# V2.net
KiCad netlist of a schematic drawn in Altium Designer
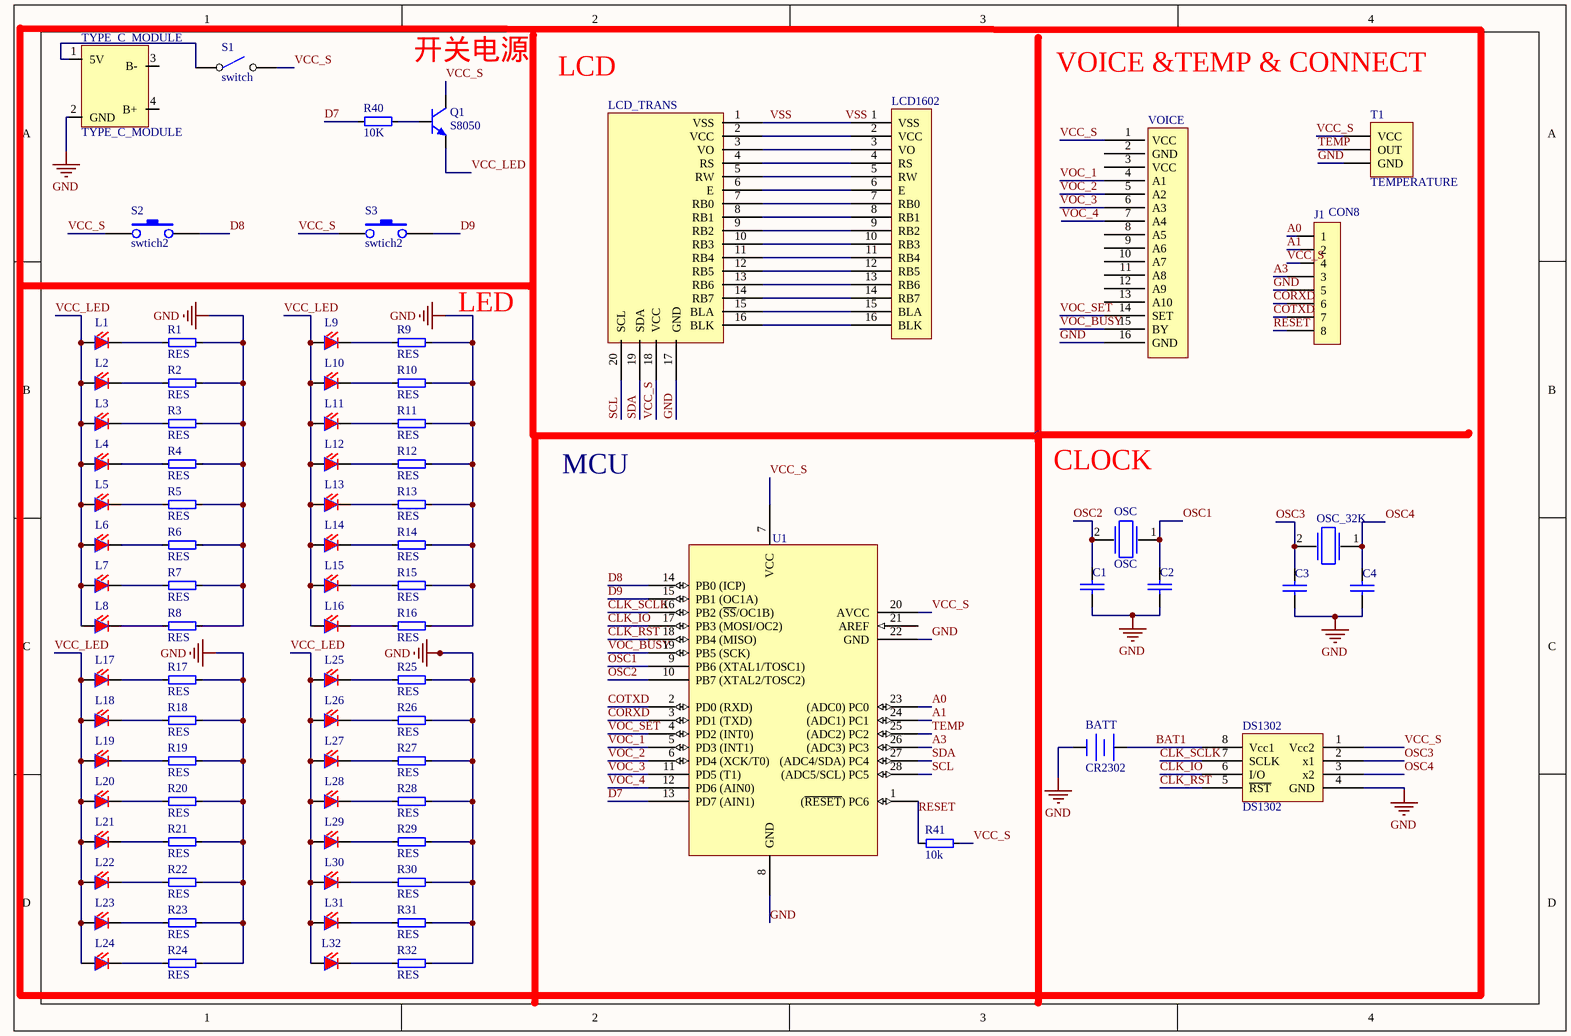
[diagram p0: 生日礼物V2.SchDoc]

(export (version "E")
  (design (tool "Eeschema 10.0.6"))
  (components
    (comp (ref "BATT")
      (value "CR2302")
      (footprint "CR2032_C")
      (description "Multicell Battery")
      (fields (field (name "PUBLISHER") "Altium Limited"))
      (libsource (lib "最小系统") (part "BATTERY"))
    )
    (comp (ref "C1") (value "~") (footprint "CAP") (libsource (lib "最小系统") (part "CAP")))
    (comp (ref "C2") (value "~") (footprint "CAP") (libsource (lib "最小系统") (part "CAP")))
    (comp (ref "C3") (value "~") (footprint "CAP") (libsource (lib "最小系统") (part "CAP")))
    (comp (ref "C4") (value "~") (footprint "CAP") (libsource (lib "最小系统") (part "CAP")))
    (comp (ref "DS1302") (value "DS1302") (footprint "DS1302") (libsource (lib "最小系统") (part "DS1302")))
    (comp (ref "J1") (value "CON8") (footprint "CON8") (libsource (lib "最小系统") (part "CON8")))
    (comp (ref "L1") (value "~") (footprint "LED 5MM-Y") (libsource (lib "最小系统") (part "LED")))
    (comp (ref "L2") (value "~") (footprint "LED 5MM-Y") (libsource (lib "最小系统") (part "LED")))
    (comp (ref "L3") (value "~") (footprint "LED 5MM-Y") (libsource (lib "最小系统") (part "LED")))
    (comp (ref "L4") (value "~") (footprint "LED 5MM-Y") (libsource (lib "最小系统") (part "LED")))
    (comp (ref "L5") (value "~") (footprint "LED 5MM-Y") (libsource (lib "最小系统") (part "LED")))
    (comp (ref "L6") (value "~") (footprint "LED 5MM-Y") (libsource (lib "最小系统") (part "LED")))
    (comp (ref "L7") (value "~") (footprint "LED 5MM-Y") (libsource (lib "最小系统") (part "LED")))
    (comp (ref "L8") (value "~") (footprint "LED 5MM-Y") (libsource (lib "最小系统") (part "LED")))
    (comp (ref "L9") (value "~") (footprint "LED 5MM-Y") (libsource (lib "最小系统") (part "LED")))
    (comp (ref "L10") (value "~") (footprint "LED 5MM-Y") (libsource (lib "最小系统") (part "LED")))
    (comp (ref "L11") (value "~") (footprint "LED 5MM-Y") (libsource (lib "最小系统") (part "LED")))
    (comp (ref "L12") (value "~") (footprint "LED 5MM-Y") (libsource (lib "最小系统") (part "LED")))
    (comp (ref "L13") (value "~") (footprint "LED 5MM-Y") (libsource (lib "最小系统") (part "LED")))
    (comp (ref "L14") (value "~") (footprint "LED 5MM-Y") (libsource (lib "最小系统") (part "LED")))
    (comp (ref "L15") (value "~") (footprint "LED 5MM-Y") (libsource (lib "最小系统") (part "LED")))
    (comp (ref "L16") (value "~") (footprint "LED 5MM-Y") (libsource (lib "最小系统") (part "LED")))
    (comp (ref "L17") (value "~") (footprint "LED 5MM-Y") (libsource (lib "最小系统") (part "LED")))
    (comp (ref "L18") (value "~") (footprint "LED 5MM-Y") (libsource (lib "最小系统") (part "LED")))
    (comp (ref "L19") (value "~") (footprint "LED 5MM-Y") (libsource (lib "最小系统") (part "LED")))
    (comp (ref "L20") (value "~") (footprint "LED 5MM-Y") (libsource (lib "最小系统") (part "LED")))
    (comp (ref "L21") (value "~") (footprint "LED 5MM-Y") (libsource (lib "最小系统") (part "LED")))
    (comp (ref "L22") (value "~") (footprint "LED 5MM-Y") (libsource (lib "最小系统") (part "LED")))
    (comp (ref "L23") (value "~") (footprint "LED 5MM-Y") (libsource (lib "最小系统") (part "LED")))
    (comp (ref "L24") (value "~") (footprint "LED 5MM-Y") (libsource (lib "最小系统") (part "LED")))
    (comp (ref "L25") (value "~") (footprint "LED 5MM-Y") (libsource (lib "最小系统") (part "LED")))
    (comp (ref "L26") (value "~") (footprint "LED 5MM-Y") (libsource (lib "最小系统") (part "LED")))
    (comp (ref "L27") (value "~") (footprint "LED 5MM-Y") (libsource (lib "最小系统") (part "LED")))
    (comp (ref "L28") (value "~") (footprint "LED 5MM-Y") (libsource (lib "最小系统") (part "LED")))
    (comp (ref "L29") (value "~") (footprint "LED 5MM-Y") (libsource (lib "最小系统") (part "LED")))
    (comp (ref "L30") (value "~") (footprint "LED 5MM-Y") (libsource (lib "最小系统") (part "LED")))
    (comp (ref "L31") (value "~") (footprint "LED 5MM-Y") (libsource (lib "最小系统") (part "LED")))
    (comp (ref "L32") (value "~") (footprint "LED 5MM-Y") (libsource (lib "最小系统") (part "LED")))
    (comp (ref "LCD1602") (value "~") (footprint "LCD1602") (libsource (lib "最小系统") (part "LCD1602")))
    (comp (ref "LCD_TRANS") (value "~") (footprint "LCD-TRANS") (libsource (lib "最小系统") (part "LCD_TRANS")))
    (comp (ref "OSC")
      (value "OSC")
      (footprint "OSC HC-49U")
      (description "晶振 32.768KHZ")
      (libsource (lib "最小系统") (part "OSC"))
    )
    (comp (ref "OSC_32K") (value "~") (footprint "osc_32.768K") (libsource (lib "生日礼物V2") (part "OSC_32K")))
    (comp (ref "Q1")
      (value "S8050")
      (footprint "TO92")
      (description "高频放大-NPN型")
      (fields (field (name "版权归属") "源创客"))
      (libsource (lib "最小系统") (part "8050-DIP"))
    )
    (comp (ref "R1") (value "RES") (footprint "0805R") (libsource (lib "最小系统") (part "RES")))
    (comp (ref "R2") (value "RES") (footprint "0805R") (libsource (lib "最小系统") (part "RES")))
    (comp (ref "R3") (value "RES") (footprint "0805R") (libsource (lib "最小系统") (part "RES")))
    (comp (ref "R4") (value "RES") (footprint "0805R") (libsource (lib "最小系统") (part "RES")))
    (comp (ref "R5") (value "RES") (footprint "0805R") (libsource (lib "最小系统") (part "RES")))
    (comp (ref "R6") (value "RES") (footprint "0805R") (libsource (lib "最小系统") (part "RES")))
    (comp (ref "R7") (value "RES") (footprint "0805R") (libsource (lib "最小系统") (part "RES")))
    (comp (ref "R8") (value "RES") (footprint "0805R") (libsource (lib "最小系统") (part "RES")))
    (comp (ref "R9") (value "RES") (footprint "0805R") (libsource (lib "最小系统") (part "RES")))
    (comp (ref "R10") (value "RES") (footprint "0805R") (libsource (lib "最小系统") (part "RES")))
    (comp (ref "R11") (value "RES") (footprint "0805R") (libsource (lib "最小系统") (part "RES")))
    (comp (ref "R12") (value "RES") (footprint "0805R") (libsource (lib "最小系统") (part "RES")))
    (comp (ref "R13") (value "RES") (footprint "0805R") (libsource (lib "最小系统") (part "RES")))
    (comp (ref "R14") (value "RES") (footprint "0805R") (libsource (lib "最小系统") (part "RES")))
    (comp (ref "R15") (value "RES") (footprint "0805R") (libsource (lib "最小系统") (part "RES")))
    (comp (ref "R16") (value "RES") (footprint "0805R") (libsource (lib "最小系统") (part "RES")))
    (comp (ref "R17") (value "RES") (footprint "0805R") (libsource (lib "最小系统") (part "RES")))
    (comp (ref "R18") (value "RES") (footprint "0805R") (libsource (lib "最小系统") (part "RES")))
    (comp (ref "R19") (value "RES") (footprint "0805R") (libsource (lib "最小系统") (part "RES")))
    (comp (ref "R20") (value "RES") (footprint "0805R") (libsource (lib "最小系统") (part "RES")))
    (comp (ref "R21") (value "RES") (footprint "0805R") (libsource (lib "最小系统") (part "RES")))
    (comp (ref "R22") (value "RES") (footprint "0805R") (libsource (lib "最小系统") (part "RES")))
    (comp (ref "R23") (value "RES") (footprint "0805R") (libsource (lib "最小系统") (part "RES")))
    (comp (ref "R24") (value "RES") (footprint "0805R") (libsource (lib "最小系统") (part "RES")))
    (comp (ref "R25") (value "RES") (footprint "0805R") (libsource (lib "最小系统") (part "RES")))
    (comp (ref "R26") (value "RES") (footprint "0805R") (libsource (lib "最小系统") (part "RES")))
    (comp (ref "R27") (value "RES") (footprint "0805R") (libsource (lib "最小系统") (part "RES")))
    (comp (ref "R28") (value "RES") (footprint "0805R") (libsource (lib "最小系统") (part "RES")))
    (comp (ref "R29") (value "RES") (footprint "0805R") (libsource (lib "最小系统") (part "RES")))
    (comp (ref "R30") (value "RES") (footprint "0805R") (libsource (lib "最小系统") (part "RES")))
    (comp (ref "R31") (value "RES") (footprint "0805R") (libsource (lib "最小系统") (part "RES")))
    (comp (ref "R32") (value "RES") (footprint "0805R") (libsource (lib "最小系统") (part "RES")))
    (comp (ref "R40") (value "10K") (footprint "0805R") (libsource (lib "最小系统") (part "RES")))
    (comp (ref "R41") (value "10k") (footprint "0805R") (libsource (lib "最小系统") (part "RES")))
    (comp (ref "S1")
      (value "switch")
      (footprint "switch")
      (description "主开关")
      (libsource (lib "最小系统") (part "switch"))
    )
    (comp (ref "S2")
      (value "swtich2")
      (footprint "switch")
      (description "按钮触发")
      (libsource (lib "最小系统") (part "swtich"))
    )
    (comp (ref "S3") (value "swtich2") (footprint "switch") (libsource (lib "最小系统") (part "swtich")))
    (comp (ref "T1")
      (value "TEMPERATURE")
      (footprint "TEMP_SENSOR")
      (description "温度传感器")
      (libsource (lib "最小系统") (part "TEMPERATURE"))
    )
    (comp (ref "TYPE_C_MODULE")
      (value "TYPE_C_MODULE")
      (footprint "TYPE_C_Module")
      (libsource (lib "最小系统") (part "TYPE_C_MODULE"))
    )
    (comp (ref "U1")
      (value "~")
      (footprint "DIP28")
      (description "Atmel Microcontroller - Library created by carel..  <www.mpfreezone.com>")
      (libsource (lib "最小系统") (part "ATMEGA8_DIP28"))
    )
    (comp (ref "VOICE") (value "~") (footprint "VOICE") (libsource (lib "最小系统") (part "VOICE")))
  )
  (nets
    (net (code "1") (name "/A0") (class "Default")
      (node (ref "J1") (pin "1") (pinfunction "1_1") (pintype "passive"))
      (node (ref "U1") (pin "23") (pinfunction "(ADC0)_PC0_23") (pintype "bidirectional"))
    )
    (net (code "2") (name "/A1") (class "Default")
      (node (ref "J1") (pin "2") (pinfunction "2_2") (pintype "passive"))
      (node (ref "U1") (pin "24") (pinfunction "(ADC1)_PC1_24") (pintype "bidirectional"))
    )
    (net (code "3") (name "/A3") (class "Default")
      (node (ref "J1") (pin "3") (pinfunction "3_3") (pintype "passive"))
      (node (ref "U1") (pin "26") (pinfunction "(ADC3)_PC3_26") (pintype "bidirectional"))
    )
    (net (code "4") (name "/BAT1") (class "Default")
      (node (ref "BATT") (pin "1") (pinfunction "+_1") (pintype "passive"))
      (node (ref "DS1302") (pin "8") (pinfunction "Vcc1_8") (pintype "passive"))
    )
    (net (code "5") (name "/CLK_IO") (class "Default")
      (node (ref "DS1302") (pin "6") (pinfunction "I/O_6") (pintype "passive"))
      (node (ref "U1") (pin "17") (pinfunction "PB3_(MOSI/OC2)_17") (pintype "bidirectional"))
    )
    (net (code "6") (name "/CLK_RST") (class "Default")
      (node (ref "DS1302") (pin "5") (pinfunction "~{RST}_5") (pintype "passive"))
      (node (ref "U1") (pin "18") (pinfunction "PB4_(MISO)_18") (pintype "bidirectional"))
    )
    (net (code "7") (name "/CLK_SCLK") (class "Default")
      (node (ref "DS1302") (pin "7") (pinfunction "SCLK_7") (pintype "passive"))
      (node (ref "U1") (pin "16") (pinfunction "PB2_(~{SS}/OC1B)_16") (pintype "bidirectional"))
    )
    (net (code "8") (name "/CORXD") (class "Default")
      (node (ref "J1") (pin "6") (pinfunction "6_6") (pintype "passive"))
      (node (ref "U1") (pin "3") (pinfunction "PD1_(TXD)_3") (pintype "bidirectional"))
    )
    (net (code "9") (name "/COTXD") (class "Default")
      (node (ref "J1") (pin "7") (pinfunction "7_7") (pintype "passive"))
      (node (ref "U1") (pin "2") (pinfunction "PD0_(RXD)_2") (pintype "bidirectional"))
    )
    (net (code "10") (name "/D7") (class "Default")
      (node (ref "R40") (pin "1") (pinfunction "1_1") (pintype "passive"))
      (node (ref "U1") (pin "13") (pinfunction "PD7_(AIN1)_13") (pintype "passive"))
    )
    (net (code "11") (name "/D8") (class "Default")
      (node (ref "S2") (pin "2") (pinfunction "2_2") (pintype "passive"))
      (node (ref "U1") (pin "14") (pinfunction "PB0_(ICP)_14") (pintype "bidirectional"))
    )
    (net (code "12") (name "/D9") (class "Default")
      (node (ref "S3") (pin "2") (pinfunction "2_2") (pintype "passive"))
      (node (ref "U1") (pin "15") (pinfunction "PB1_(OC1A)_15") (pintype "bidirectional"))
    )
    (net (code "13") (name "/OSC1") (class "Default")
      (node (ref "C2") (pin "1") (pinfunction "1_1") (pintype "passive"))
      (node (ref "OSC") (pin "1") (pintype "passive"))
      (node (ref "U1") (pin "9") (pinfunction "PB6_(XTAL1/TOSC1)_9") (pintype "passive"))
    )
    (net (code "14") (name "/OSC2") (class "Default")
      (node (ref "C1") (pin "1") (pinfunction "1_1") (pintype "passive"))
      (node (ref "OSC") (pin "2") (pintype "passive"))
      (node (ref "U1") (pin "10") (pinfunction "PB7_(XTAL2/TOSC2)_10") (pintype "passive"))
    )
    (net (code "15") (name "/OSC3") (class "Default")
      (node (ref "C3") (pin "1") (pinfunction "1_1") (pintype "passive"))
      (node (ref "DS1302") (pin "2") (pinfunction "x1_2") (pintype "passive"))
      (node (ref "OSC_32K") (pin "2") (pintype "passive"))
    )
    (net (code "16") (name "/OSC4") (class "Default")
      (node (ref "C4") (pin "1") (pinfunction "1_1") (pintype "passive"))
      (node (ref "DS1302") (pin "3") (pinfunction "x2_3") (pintype "passive"))
      (node (ref "OSC_32K") (pin "1") (pintype "passive"))
    )
    (net (code "17") (name "/RESET") (class "Default")
      (node (ref "J1") (pin "8") (pinfunction "8_8") (pintype "passive"))
      (node (ref "R41") (pin "1") (pinfunction "1_1") (pintype "passive"))
      (node (ref "U1") (pin "1") (pinfunction "(~{RESET})_PC6_1") (pintype "bidirectional"))
    )
    (net (code "18") (name "/SCL") (class "Default")
      (node (ref "LCD_TRANS") (pin "20") (pinfunction "SCL_20") (pintype "passive"))
      (node (ref "U1") (pin "28") (pinfunction "(ADC5/SCL)_PC5_28") (pintype "bidirectional"))
    )
    (net (code "19") (name "/SDA") (class "Default")
      (node (ref "LCD_TRANS") (pin "19") (pinfunction "SDA_19") (pintype "passive"))
      (node (ref "U1") (pin "27") (pinfunction "(ADC4/SDA)_PC4_27") (pintype "bidirectional"))
    )
    (net (code "20") (name "/TEMP") (class "Default")
      (node (ref "T1") (pin "2") (pinfunction "OUT_2") (pintype "passive"))
      (node (ref "U1") (pin "25") (pinfunction "(ADC2)_PC2_25") (pintype "bidirectional"))
    )
    (net (code "21") (name "/VCC_LED") (class "Default")
      (node (ref "L1") (pin "1") (pinfunction "A_1") (pintype "passive"))
      (node (ref "L10") (pin "1") (pinfunction "A_1") (pintype "passive"))
      (node (ref "L11") (pin "1") (pinfunction "A_1") (pintype "passive"))
      (node (ref "L12") (pin "1") (pinfunction "A_1") (pintype "passive"))
      (node (ref "L13") (pin "1") (pinfunction "A_1") (pintype "passive"))
      (node (ref "L14") (pin "1") (pinfunction "A_1") (pintype "passive"))
      (node (ref "L15") (pin "1") (pinfunction "A_1") (pintype "passive"))
      (node (ref "L16") (pin "1") (pinfunction "A_1") (pintype "passive"))
      (node (ref "L17") (pin "1") (pinfunction "A_1") (pintype "passive"))
      (node (ref "L18") (pin "1") (pinfunction "A_1") (pintype "passive"))
      (node (ref "L19") (pin "1") (pinfunction "A_1") (pintype "passive"))
      (node (ref "L2") (pin "1") (pinfunction "A_1") (pintype "passive"))
      (node (ref "L20") (pin "1") (pinfunction "A_1") (pintype "passive"))
      (node (ref "L21") (pin "1") (pinfunction "A_1") (pintype "passive"))
      (node (ref "L22") (pin "1") (pinfunction "A_1") (pintype "passive"))
      (node (ref "L23") (pin "1") (pinfunction "A_1") (pintype "passive"))
      (node (ref "L24") (pin "1") (pinfunction "A_1") (pintype "passive"))
      (node (ref "L25") (pin "1") (pinfunction "A_1") (pintype "passive"))
      (node (ref "L26") (pin "1") (pinfunction "A_1") (pintype "passive"))
      (node (ref "L27") (pin "1") (pinfunction "A_1") (pintype "passive"))
      (node (ref "L28") (pin "1") (pinfunction "A_1") (pintype "passive"))
      (node (ref "L29") (pin "1") (pinfunction "A_1") (pintype "passive"))
      (node (ref "L3") (pin "1") (pinfunction "A_1") (pintype "passive"))
      (node (ref "L30") (pin "1") (pinfunction "A_1") (pintype "passive"))
      (node (ref "L31") (pin "1") (pinfunction "A_1") (pintype "passive"))
      (node (ref "L32") (pin "1") (pinfunction "A_1") (pintype "passive"))
      (node (ref "L4") (pin "1") (pinfunction "A_1") (pintype "passive"))
      (node (ref "L5") (pin "1") (pinfunction "A_1") (pintype "passive"))
      (node (ref "L6") (pin "1") (pinfunction "A_1") (pintype "passive"))
      (node (ref "L7") (pin "1") (pinfunction "A_1") (pintype "passive"))
      (node (ref "L8") (pin "1") (pinfunction "A_1") (pintype "passive"))
      (node (ref "L9") (pin "1") (pinfunction "A_1") (pintype "passive"))
      (node (ref "Q1") (pin "1") (pinfunction "E_1") (pintype "passive"))
    )
    (net (code "22") (name "/VCC_S") (class "Default")
      (node (ref "DS1302") (pin "1") (pinfunction "Vcc2_1") (pintype "passive"))
      (node (ref "J1") (pin "4") (pinfunction "4_4") (pintype "passive"))
      (node (ref "LCD_TRANS") (pin "18") (pinfunction "VCC_18") (pintype "passive"))
      (node (ref "Q1") (pin "3") (pinfunction "C_3") (pintype "passive"))
      (node (ref "R41") (pin "2") (pinfunction "2_2") (pintype "passive"))
      (node (ref "S1") (pin "2") (pinfunction "2_2") (pintype "passive"))
      (node (ref "S2") (pin "1") (pinfunction "1_1") (pintype "passive"))
      (node (ref "S3") (pin "1") (pinfunction "1_1") (pintype "passive"))
      (node (ref "T1") (pin "1") (pinfunction "VCC_1") (pintype "passive"))
      (node (ref "U1") (pin "20") (pinfunction "AVCC_20") (pintype "passive"))
      (node (ref "U1") (pin "7") (pinfunction "VCC_7") (pintype "passive"))
      (node (ref "VOICE") (pin "1") (pinfunction "VCC_1") (pintype "passive"))
    )
    (net (code "23") (name "/VOC_1") (class "Default")
      (node (ref "U1") (pin "5") (pinfunction "PD3_(INT1)_5") (pintype "bidirectional"))
      (node (ref "VOICE") (pin "4") (pinfunction "A1_4") (pintype "passive"))
    )
    (net (code "24") (name "/VOC_2") (class "Default")
      (node (ref "U1") (pin "6") (pinfunction "PD4_(XCK/T0)_6") (pintype "bidirectional"))
      (node (ref "VOICE") (pin "5") (pinfunction "A2_5") (pintype "passive"))
    )
    (net (code "25") (name "/VOC_3") (class "Default")
      (node (ref "U1") (pin "11") (pinfunction "PD5_(T1)_11") (pintype "passive"))
      (node (ref "VOICE") (pin "6") (pinfunction "A3_6") (pintype "passive"))
    )
    (net (code "26") (name "/VOC_4") (class "Default")
      (node (ref "U1") (pin "12") (pinfunction "PD6_(AIN0)_12") (pintype "passive"))
      (node (ref "VOICE") (pin "7") (pinfunction "A4_7") (pintype "passive"))
    )
    (net (code "27") (name "/VOC_BUSY") (class "Default")
      (node (ref "U1") (pin "19") (pinfunction "PB5_(SCK)_19") (pintype "bidirectional"))
      (node (ref "VOICE") (pin "15") (pinfunction "BY_15") (pintype "passive"))
    )
    (net (code "28") (name "/VOC_SET") (class "Default")
      (node (ref "U1") (pin "4") (pinfunction "PD2_(INT0)_4") (pintype "bidirectional"))
      (node (ref "VOICE") (pin "14") (pinfunction "SET_14") (pintype "passive"))
    )
    (net (code "29") (name "/VSS") (class "Default")
      (node (ref "LCD1602") (pin "1") (pinfunction "VSS_1") (pintype "passive"))
      (node (ref "LCD_TRANS") (pin "1") (pinfunction "VSS_1") (pintype "passive"))
    )
    (net (code "30") (name "GND") (class "Default")
      (node (ref "BATT") (pin "2") (pinfunction "-_2") (pintype "passive"))
      (node (ref "C1") (pin "2") (pinfunction "2_2") (pintype "passive"))
      (node (ref "C2") (pin "2") (pinfunction "2_2") (pintype "passive"))
      (node (ref "C3") (pin "2") (pinfunction "2_2") (pintype "passive"))
      (node (ref "C4") (pin "2") (pinfunction "2_2") (pintype "passive"))
      (node (ref "DS1302") (pin "4") (pinfunction "GND_4") (pintype "passive"))
      (node (ref "J1") (pin "5") (pinfunction "5_5") (pintype "passive"))
      (node (ref "LCD_TRANS") (pin "17") (pinfunction "GND_17") (pintype "passive"))
      (node (ref "R1") (pin "2") (pinfunction "2_2") (pintype "passive"))
      (node (ref "R10") (pin "2") (pinfunction "2_2") (pintype "passive"))
      (node (ref "R11") (pin "2") (pinfunction "2_2") (pintype "passive"))
      (node (ref "R12") (pin "2") (pinfunction "2_2") (pintype "passive"))
      (node (ref "R13") (pin "2") (pinfunction "2_2") (pintype "passive"))
      (node (ref "R14") (pin "2") (pinfunction "2_2") (pintype "passive"))
      (node (ref "R15") (pin "2") (pinfunction "2_2") (pintype "passive"))
      (node (ref "R16") (pin "2") (pinfunction "2_2") (pintype "passive"))
      (node (ref "R17") (pin "2") (pinfunction "2_2") (pintype "passive"))
      (node (ref "R18") (pin "2") (pinfunction "2_2") (pintype "passive"))
      (node (ref "R19") (pin "2") (pinfunction "2_2") (pintype "passive"))
      (node (ref "R2") (pin "2") (pinfunction "2_2") (pintype "passive"))
      (node (ref "R20") (pin "2") (pinfunction "2_2") (pintype "passive"))
      (node (ref "R21") (pin "2") (pinfunction "2_2") (pintype "passive"))
      (node (ref "R22") (pin "2") (pinfunction "2_2") (pintype "passive"))
      (node (ref "R23") (pin "2") (pinfunction "2_2") (pintype "passive"))
      (node (ref "R24") (pin "2") (pinfunction "2_2") (pintype "passive"))
      (node (ref "R25") (pin "2") (pinfunction "2_2") (pintype "passive"))
      (node (ref "R26") (pin "2") (pinfunction "2_2") (pintype "passive"))
      (node (ref "R27") (pin "2") (pinfunction "2_2") (pintype "passive"))
      (node (ref "R28") (pin "2") (pinfunction "2_2") (pintype "passive"))
      (node (ref "R29") (pin "2") (pinfunction "2_2") (pintype "passive"))
      (node (ref "R3") (pin "2") (pinfunction "2_2") (pintype "passive"))
      (node (ref "R30") (pin "2") (pinfunction "2_2") (pintype "passive"))
      (node (ref "R31") (pin "2") (pinfunction "2_2") (pintype "passive"))
      (node (ref "R32") (pin "2") (pinfunction "2_2") (pintype "passive"))
      (node (ref "R4") (pin "2") (pinfunction "2_2") (pintype "passive"))
      (node (ref "R5") (pin "2") (pinfunction "2_2") (pintype "passive"))
      (node (ref "R6") (pin "2") (pinfunction "2_2") (pintype "passive"))
      (node (ref "R7") (pin "2") (pinfunction "2_2") (pintype "passive"))
      (node (ref "R8") (pin "2") (pinfunction "2_2") (pintype "passive"))
      (node (ref "R9") (pin "2") (pinfunction "2_2") (pintype "passive"))
      (node (ref "T1") (pin "3") (pinfunction "GND_3") (pintype "passive"))
      (node (ref "TYPE_C_MODULE") (pin "2") (pinfunction "GND_2") (pintype "passive"))
      (node (ref "U1") (pin "22") (pinfunction "GND_22") (pintype "passive"))
      (node (ref "U1") (pin "8") (pinfunction "GND_8") (pintype "passive"))
      (node (ref "VOICE") (pin "16") (pinfunction "GND_16") (pintype "passive"))
    )
    (net (code "31") (name "Net-(L1-K)") (class "Default")
      (node (ref "L1") (pin "2") (pinfunction "K_2") (pintype "passive"))
      (node (ref "R1") (pin "1") (pinfunction "1_1") (pintype "passive"))
    )
    (net (code "32") (name "Net-(L2-K)") (class "Default")
      (node (ref "L2") (pin "2") (pinfunction "K_2") (pintype "passive"))
      (node (ref "R2") (pin "1") (pinfunction "1_1") (pintype "passive"))
    )
    (net (code "33") (name "Net-(L3-K)") (class "Default")
      (node (ref "L3") (pin "2") (pinfunction "K_2") (pintype "passive"))
      (node (ref "R3") (pin "1") (pinfunction "1_1") (pintype "passive"))
    )
    (net (code "34") (name "Net-(L4-K)") (class "Default")
      (node (ref "L4") (pin "2") (pinfunction "K_2") (pintype "passive"))
      (node (ref "R4") (pin "1") (pinfunction "1_1") (pintype "passive"))
    )
    (net (code "35") (name "Net-(L5-K)") (class "Default")
      (node (ref "L5") (pin "2") (pinfunction "K_2") (pintype "passive"))
      (node (ref "R5") (pin "1") (pinfunction "1_1") (pintype "passive"))
    )
    (net (code "36") (name "Net-(L6-K)") (class "Default")
      (node (ref "L6") (pin "2") (pinfunction "K_2") (pintype "passive"))
      (node (ref "R6") (pin "1") (pinfunction "1_1") (pintype "passive"))
    )
    (net (code "37") (name "Net-(L7-K)") (class "Default")
      (node (ref "L7") (pin "2") (pinfunction "K_2") (pintype "passive"))
      (node (ref "R7") (pin "1") (pinfunction "1_1") (pintype "passive"))
    )
    (net (code "38") (name "Net-(L8-K)") (class "Default")
      (node (ref "L8") (pin "2") (pinfunction "K_2") (pintype "passive"))
      (node (ref "R8") (pin "1") (pinfunction "1_1") (pintype "passive"))
    )
    (net (code "39") (name "Net-(L9-K)") (class "Default")
      (node (ref "L9") (pin "2") (pinfunction "K_2") (pintype "passive"))
      (node (ref "R9") (pin "1") (pinfunction "1_1") (pintype "passive"))
    )
    (net (code "40") (name "Net-(L10-K)") (class "Default")
      (node (ref "L10") (pin "2") (pinfunction "K_2") (pintype "passive"))
      (node (ref "R10") (pin "1") (pinfunction "1_1") (pintype "passive"))
    )
    (net (code "41") (name "Net-(L11-K)") (class "Default")
      (node (ref "L11") (pin "2") (pinfunction "K_2") (pintype "passive"))
      (node (ref "R11") (pin "1") (pinfunction "1_1") (pintype "passive"))
    )
    (net (code "42") (name "Net-(L12-K)") (class "Default")
      (node (ref "L12") (pin "2") (pinfunction "K_2") (pintype "passive"))
      (node (ref "R12") (pin "1") (pinfunction "1_1") (pintype "passive"))
    )
    (net (code "43") (name "Net-(L13-K)") (class "Default")
      (node (ref "L13") (pin "2") (pinfunction "K_2") (pintype "passive"))
      (node (ref "R13") (pin "1") (pinfunction "1_1") (pintype "passive"))
    )
    (net (code "44") (name "Net-(L14-K)") (class "Default")
      (node (ref "L14") (pin "2") (pinfunction "K_2") (pintype "passive"))
      (node (ref "R14") (pin "1") (pinfunction "1_1") (pintype "passive"))
    )
    (net (code "45") (name "Net-(L15-K)") (class "Default")
      (node (ref "L15") (pin "2") (pinfunction "K_2") (pintype "passive"))
      (node (ref "R15") (pin "1") (pinfunction "1_1") (pintype "passive"))
    )
    (net (code "46") (name "Net-(L16-K)") (class "Default")
      (node (ref "L16") (pin "2") (pinfunction "K_2") (pintype "passive"))
      (node (ref "R16") (pin "1") (pinfunction "1_1") (pintype "passive"))
    )
    (net (code "47") (name "Net-(L17-K)") (class "Default")
      (node (ref "L17") (pin "2") (pinfunction "K_2") (pintype "passive"))
      (node (ref "R17") (pin "1") (pinfunction "1_1") (pintype "passive"))
    )
    (net (code "48") (name "Net-(L18-K)") (class "Default")
      (node (ref "L18") (pin "2") (pinfunction "K_2") (pintype "passive"))
      (node (ref "R18") (pin "1") (pinfunction "1_1") (pintype "passive"))
    )
    (net (code "49") (name "Net-(L19-K)") (class "Default")
      (node (ref "L19") (pin "2") (pinfunction "K_2") (pintype "passive"))
      (node (ref "R19") (pin "1") (pinfunction "1_1") (pintype "passive"))
    )
    (net (code "50") (name "Net-(L20-K)") (class "Default")
      (node (ref "L20") (pin "2") (pinfunction "K_2") (pintype "passive"))
      (node (ref "R20") (pin "1") (pinfunction "1_1") (pintype "passive"))
    )
    (net (code "51") (name "Net-(L21-K)") (class "Default")
      (node (ref "L21") (pin "2") (pinfunction "K_2") (pintype "passive"))
      (node (ref "R21") (pin "1") (pinfunction "1_1") (pintype "passive"))
    )
    (net (code "52") (name "Net-(L22-K)") (class "Default")
      (node (ref "L22") (pin "2") (pinfunction "K_2") (pintype "passive"))
      (node (ref "R22") (pin "1") (pinfunction "1_1") (pintype "passive"))
    )
    (net (code "53") (name "Net-(L23-K)") (class "Default")
      (node (ref "L23") (pin "2") (pinfunction "K_2") (pintype "passive"))
      (node (ref "R23") (pin "1") (pinfunction "1_1") (pintype "passive"))
    )
    (net (code "54") (name "Net-(L24-K)") (class "Default")
      (node (ref "L24") (pin "2") (pinfunction "K_2") (pintype "passive"))
      (node (ref "R24") (pin "1") (pinfunction "1_1") (pintype "passive"))
    )
    (net (code "55") (name "Net-(L25-K)") (class "Default")
      (node (ref "L25") (pin "2") (pinfunction "K_2") (pintype "passive"))
      (node (ref "R25") (pin "1") (pinfunction "1_1") (pintype "passive"))
    )
    (net (code "56") (name "Net-(L26-K)") (class "Default")
      (node (ref "L26") (pin "2") (pinfunction "K_2") (pintype "passive"))
      (node (ref "R26") (pin "1") (pinfunction "1_1") (pintype "passive"))
    )
    (net (code "57") (name "Net-(L27-K)") (class "Default")
      (node (ref "L27") (pin "2") (pinfunction "K_2") (pintype "passive"))
      (node (ref "R27") (pin "1") (pinfunction "1_1") (pintype "passive"))
    )
    (net (code "58") (name "Net-(L28-K)") (class "Default")
      (node (ref "L28") (pin "2") (pinfunction "K_2") (pintype "passive"))
      (node (ref "R28") (pin "1") (pinfunction "1_1") (pintype "passive"))
    )
    (net (code "59") (name "Net-(L29-K)") (class "Default")
      (node (ref "L29") (pin "2") (pinfunction "K_2") (pintype "passive"))
      (node (ref "R29") (pin "1") (pinfunction "1_1") (pintype "passive"))
    )
    (net (code "60") (name "Net-(L30-K)") (class "Default")
      (node (ref "L30") (pin "2") (pinfunction "K_2") (pintype "passive"))
      (node (ref "R30") (pin "1") (pinfunction "1_1") (pintype "passive"))
    )
    (net (code "61") (name "Net-(L31-K)") (class "Default")
      (node (ref "L31") (pin "2") (pinfunction "K_2") (pintype "passive"))
      (node (ref "R31") (pin "1") (pinfunction "1_1") (pintype "passive"))
    )
    (net (code "62") (name "Net-(L32-K)") (class "Default")
      (node (ref "L32") (pin "2") (pinfunction "K_2") (pintype "passive"))
      (node (ref "R32") (pin "1") (pinfunction "1_1") (pintype "passive"))
    )
    (net (code "63") (name "Net-(LCD1602-BLA)") (class "Default")
      (node (ref "LCD1602") (pin "15") (pinfunction "BLA_15") (pintype "passive"))
      (node (ref "LCD_TRANS") (pin "15") (pinfunction "BLA_15") (pintype "passive"))
    )
    (net (code "64") (name "Net-(LCD1602-BLK)") (class "Default")
      (node (ref "LCD1602") (pin "16") (pinfunction "BLK_16") (pintype "passive"))
      (node (ref "LCD_TRANS") (pin "16") (pinfunction "BLK_16") (pintype "passive"))
    )
    (net (code "65") (name "Net-(LCD1602-E)") (class "Default")
      (node (ref "LCD1602") (pin "6") (pinfunction "E_6") (pintype "passive"))
      (node (ref "LCD_TRANS") (pin "6") (pinfunction "E_6") (pintype "passive"))
    )
    (net (code "66") (name "Net-(LCD1602-RB0)") (class "Default")
      (node (ref "LCD1602") (pin "7") (pinfunction "RB0_7") (pintype "passive"))
      (node (ref "LCD_TRANS") (pin "7") (pinfunction "RB0_7") (pintype "passive"))
    )
    (net (code "67") (name "Net-(LCD1602-RB1)") (class "Default")
      (node (ref "LCD1602") (pin "8") (pinfunction "RB1_8") (pintype "passive"))
      (node (ref "LCD_TRANS") (pin "8") (pinfunction "RB1_8") (pintype "passive"))
    )
    (net (code "68") (name "Net-(LCD1602-RB2)") (class "Default")
      (node (ref "LCD1602") (pin "9") (pinfunction "RB2_9") (pintype "passive"))
      (node (ref "LCD_TRANS") (pin "9") (pinfunction "RB2_9") (pintype "passive"))
    )
    (net (code "69") (name "Net-(LCD1602-RB3)") (class "Default")
      (node (ref "LCD1602") (pin "10") (pinfunction "RB3_10") (pintype "passive"))
      (node (ref "LCD_TRANS") (pin "10") (pinfunction "RB3_10") (pintype "passive"))
    )
    (net (code "70") (name "Net-(LCD1602-RB4)") (class "Default")
      (node (ref "LCD1602") (pin "11") (pinfunction "RB4_11") (pintype "passive"))
      (node (ref "LCD_TRANS") (pin "11") (pinfunction "RB4_11") (pintype "passive"))
    )
    (net (code "71") (name "Net-(LCD1602-RB5)") (class "Default")
      (node (ref "LCD1602") (pin "12") (pinfunction "RB5_12") (pintype "passive"))
      (node (ref "LCD_TRANS") (pin "12") (pinfunction "RB5_12") (pintype "passive"))
    )
    (net (code "72") (name "Net-(LCD1602-RB6)") (class "Default")
      (node (ref "LCD1602") (pin "13") (pinfunction "RB6_13") (pintype "passive"))
      (node (ref "LCD_TRANS") (pin "13") (pinfunction "RB6_13") (pintype "passive"))
    )
    (net (code "73") (name "Net-(LCD1602-RB7)") (class "Default")
      (node (ref "LCD1602") (pin "14") (pinfunction "RB7_14") (pintype "passive"))
      (node (ref "LCD_TRANS") (pin "14") (pinfunction "RB7_14") (pintype "passive"))
    )
    (net (code "74") (name "Net-(LCD1602-RS)") (class "Default")
      (node (ref "LCD1602") (pin "4") (pinfunction "RS_4") (pintype "passive"))
      (node (ref "LCD_TRANS") (pin "4") (pinfunction "RS_4") (pintype "passive"))
    )
    (net (code "75") (name "Net-(LCD1602-RW)") (class "Default")
      (node (ref "LCD1602") (pin "5") (pinfunction "RW_5") (pintype "passive"))
      (node (ref "LCD_TRANS") (pin "5") (pinfunction "RW_5") (pintype "passive"))
    )
    (net (code "76") (name "Net-(LCD1602-VCC)") (class "Default")
      (node (ref "LCD1602") (pin "2") (pinfunction "VCC_2") (pintype "passive"))
      (node (ref "LCD_TRANS") (pin "2") (pinfunction "VCC_2") (pintype "passive"))
    )
    (net (code "77") (name "Net-(LCD1602-VO)") (class "Default")
      (node (ref "LCD1602") (pin "3") (pinfunction "VO_3") (pintype "passive"))
      (node (ref "LCD_TRANS") (pin "3") (pinfunction "VO_3") (pintype "passive"))
    )
    (net (code "78") (name "Net-(Q1-B)") (class "Default")
      (node (ref "Q1") (pin "2") (pinfunction "B_2") (pintype "passive"))
      (node (ref "R40") (pin "2") (pinfunction "2_2") (pintype "passive"))
    )
    (net (code "79") (name "Net-(TYPE_C_MODULE-5V)") (class "Default")
      (node (ref "S1") (pin "1") (pinfunction "1_1") (pintype "passive"))
      (node (ref "TYPE_C_MODULE") (pin "1") (pinfunction "5V_1") (pintype "passive"))
    )
    (net (code "80") (name "unconnected-(TYPE_C_MODULE-B+-Pad4)") (class "Default")
      (node (ref "TYPE_C_MODULE") (pin "4") (pinfunction "B+_4") (pintype "passive"))
    )
    (net (code "81") (name "unconnected-(TYPE_C_MODULE-B--Pad3)") (class "Default")
      (node (ref "TYPE_C_MODULE") (pin "3") (pinfunction "B-_3") (pintype "passive"))
    )
    (net (code "82") (name "unconnected-(U1-AREF-Pad21)") (class "Default")
      (node (ref "U1") (pin "21") (pinfunction "AREF_21") (pintype "input"))
    )
    (net (code "83") (name "unconnected-(VOICE-A5-Pad8)") (class "Default")
      (node (ref "VOICE") (pin "8") (pinfunction "A5_8") (pintype "passive"))
    )
    (net (code "84") (name "unconnected-(VOICE-A6-Pad9)") (class "Default")
      (node (ref "VOICE") (pin "9") (pinfunction "A6_9") (pintype "passive"))
    )
    (net (code "85") (name "unconnected-(VOICE-A7-Pad10)") (class "Default")
      (node (ref "VOICE") (pin "10") (pinfunction "A7_10") (pintype "passive"))
    )
    (net (code "86") (name "unconnected-(VOICE-A8-Pad11)") (class "Default")
      (node (ref "VOICE") (pin "11") (pinfunction "A8_11") (pintype "passive"))
    )
    (net (code "87") (name "unconnected-(VOICE-A9-Pad12)") (class "Default")
      (node (ref "VOICE") (pin "12") (pinfunction "A9_12") (pintype "passive"))
    )
    (net (code "88") (name "unconnected-(VOICE-A10-Pad13)") (class "Default")
      (node (ref "VOICE") (pin "13") (pinfunction "A10_13") (pintype "passive"))
    )
    (net (code "89") (name "unconnected-(VOICE-GND-Pad2)") (class "Default")
      (node (ref "VOICE") (pin "2") (pinfunction "GND_2") (pintype "passive"))
    )
    (net (code "90") (name "unconnected-(VOICE-VCC-Pad3)") (class "Default")
      (node (ref "VOICE") (pin "3") (pinfunction "VCC_3") (pintype "passive"))
    )
  )
)
